# Main.net
KiCad netlist of a schematic drawn in Altium Designer
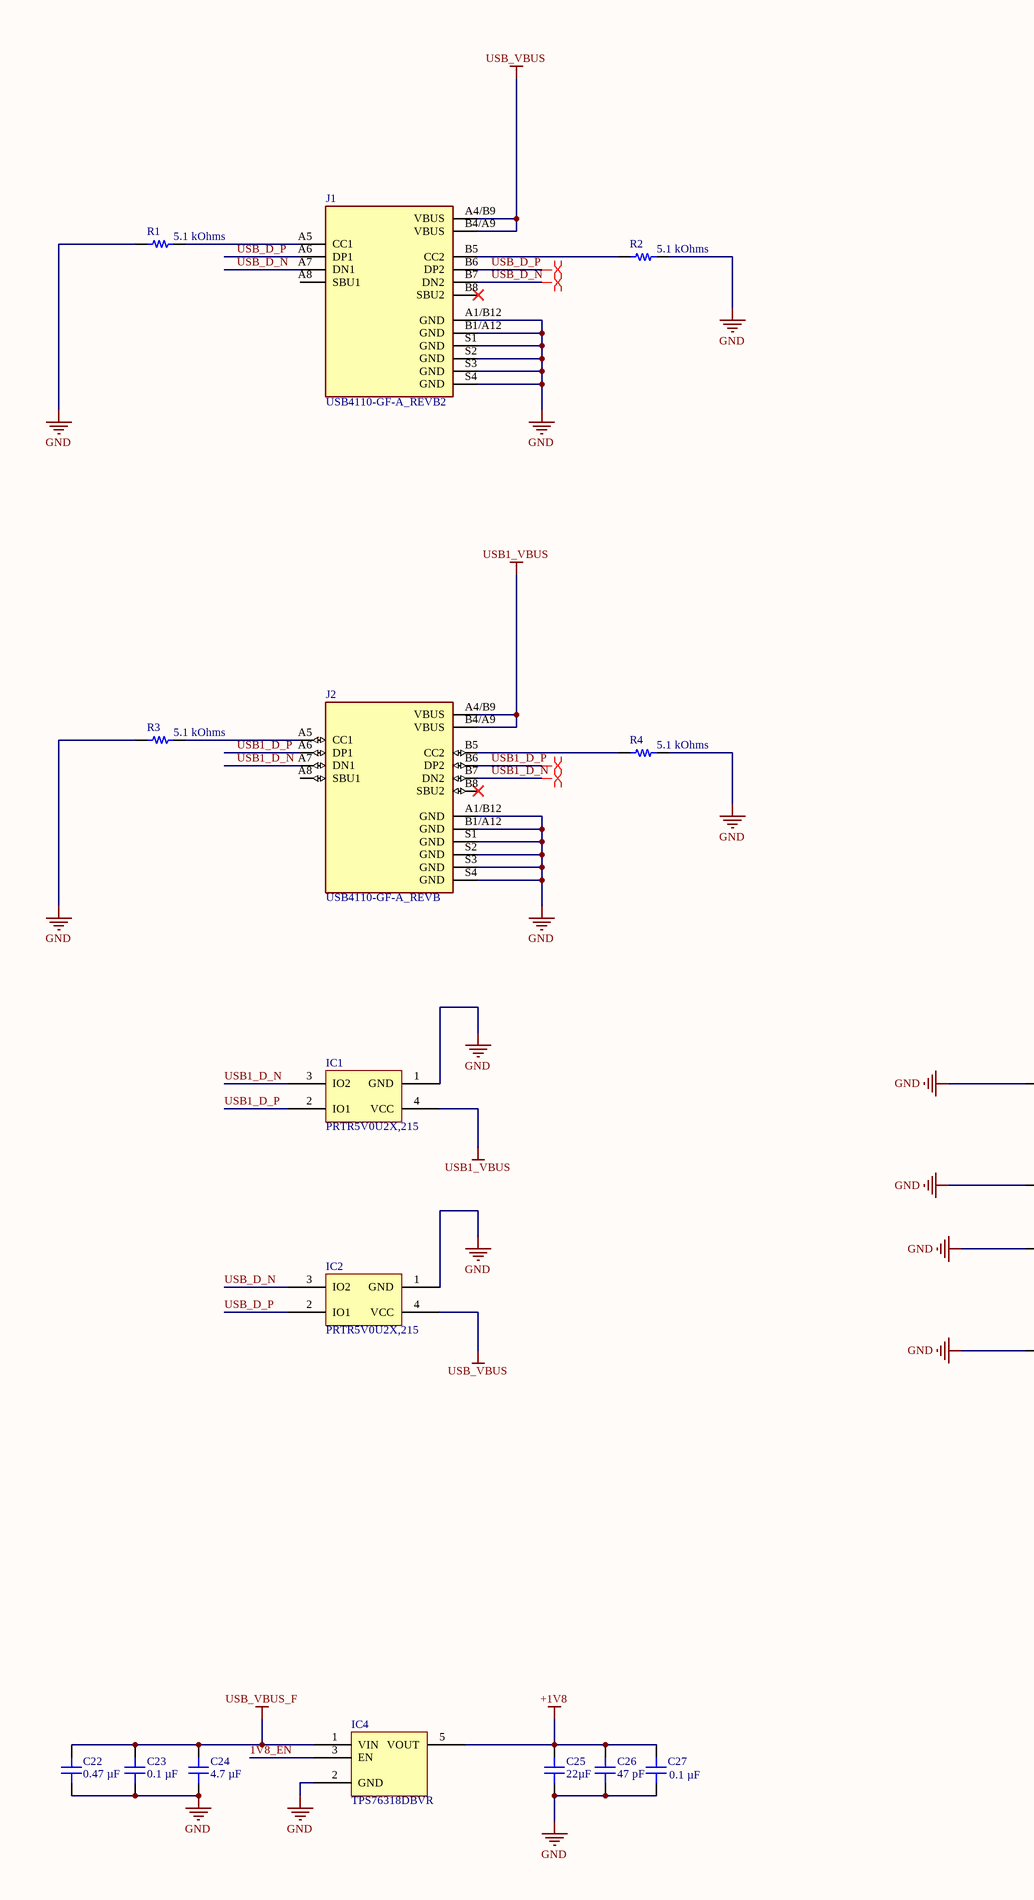
[diagram p0: Main.SchDoc, left]
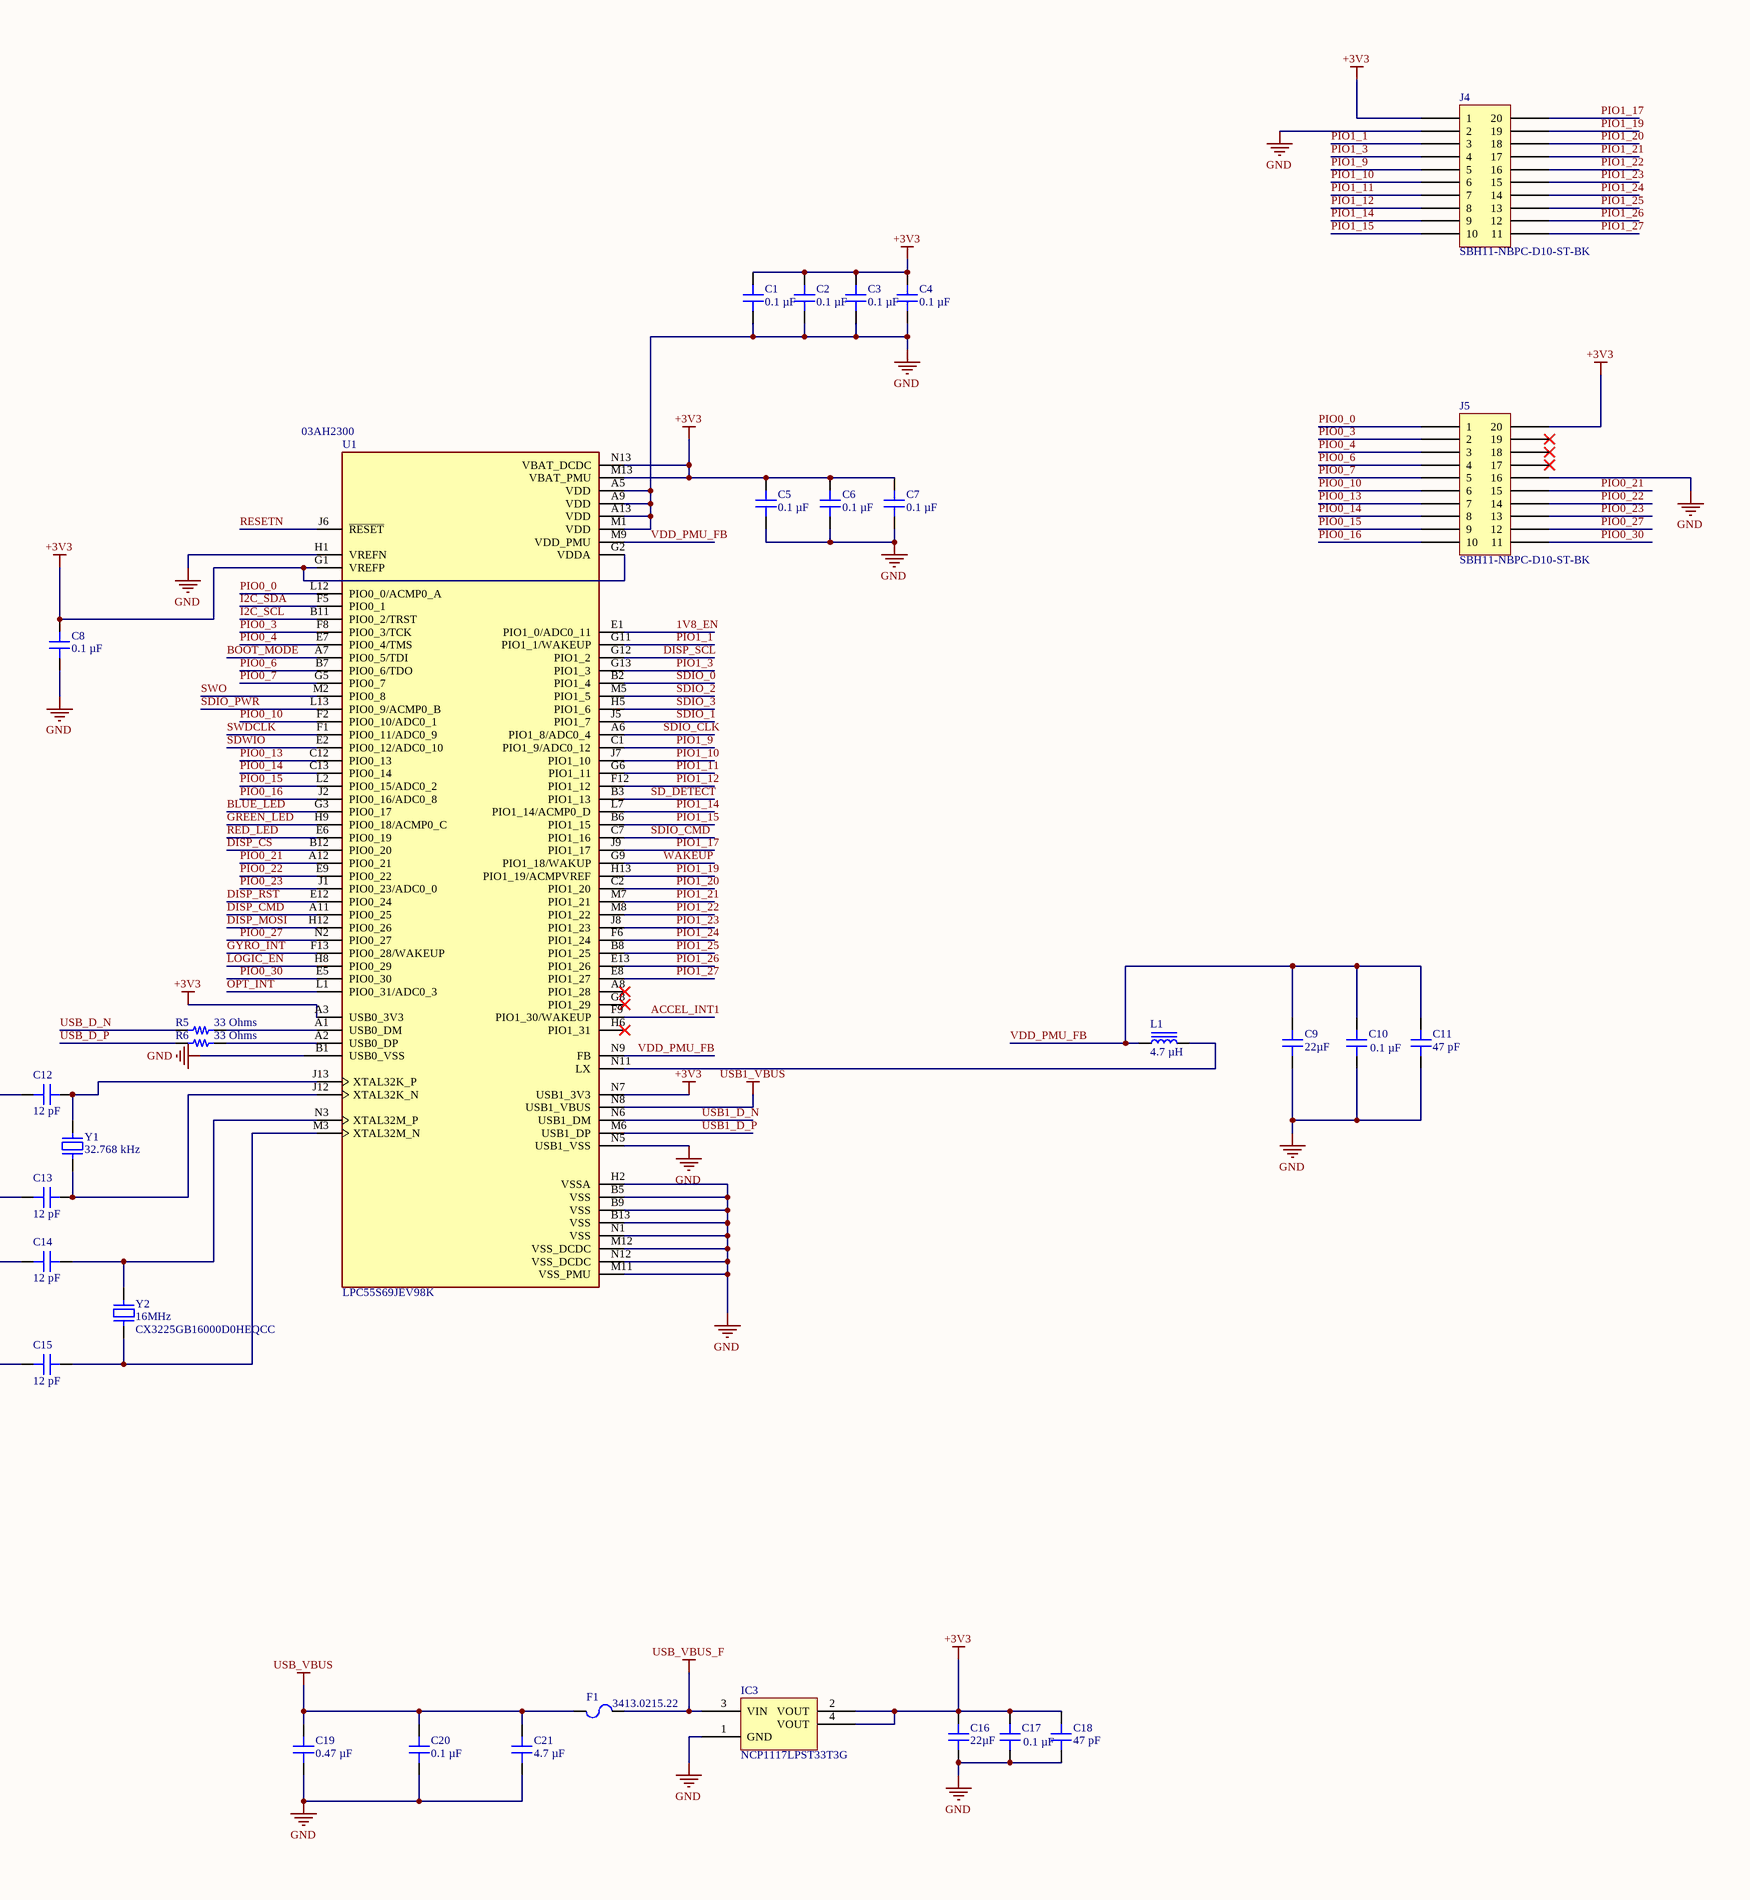
[diagram p1: Main.SchDoc, right]

(export (version "E")
  (design (tool "Eeschema 10.0.6"))
  (components
    (comp (ref "C1")
      (value "0.1 µF")
      (footprint "CAP 0603_1608")
      (description "CAP CER 0.1UF 16V X7R 0603")
      (fields (field (name "PART NUMBER") "CS0603KRX7R7BB104") (field (name "MANUFACTURER") "Yageo"))
      (libsource (lib "Celestial Altium Library - altium_library") (part "Capacitor"))
    )
    (comp (ref "C2")
      (value "0.1 µF")
      (footprint "CAP 0603_1608")
      (description "CAP CER 0.1UF 16V X7R 0603")
      (fields (field (name "PART NUMBER") "CS0603KRX7R7BB104") (field (name "MANUFACTURER") "Yageo"))
      (libsource (lib "Celestial Altium Library - altium_library") (part "Capacitor"))
    )
    (comp (ref "C3")
      (value "0.1 µF")
      (footprint "CAP 0603_1608")
      (description "CAP CER 0.1UF 16V X7R 0603")
      (fields (field (name "PART NUMBER") "CS0603KRX7R7BB104") (field (name "MANUFACTURER") "Yageo"))
      (libsource (lib "Celestial Altium Library - altium_library") (part "Capacitor"))
    )
    (comp (ref "C4")
      (value "0.1 µF")
      (footprint "CAP 0603_1608")
      (description "CAP CER 0.1UF 16V X7R 0603")
      (fields (field (name "PART NUMBER") "CS0603KRX7R7BB104") (field (name "MANUFACTURER") "Yageo"))
      (libsource (lib "Celestial Altium Library - altium_library") (part "Capacitor"))
    )
    (comp (ref "C5")
      (value "0.1 µF")
      (footprint "CAP 0603_1608")
      (description "CAP CER 0.1UF 16V X7R 0603")
      (fields (field (name "PART NUMBER") "CS0603KRX7R7BB104") (field (name "MANUFACTURER") "Yageo"))
      (libsource (lib "Celestial Altium Library - altium_library") (part "Capacitor"))
    )
    (comp (ref "C6")
      (value "0.1 µF")
      (footprint "CAP 0603_1608")
      (description "CAP CER 0.1UF 16V X7R 0603")
      (fields (field (name "PART NUMBER") "CS0603KRX7R7BB104") (field (name "MANUFACTURER") "Yageo"))
      (libsource (lib "Celestial Altium Library - altium_library") (part "Capacitor"))
    )
    (comp (ref "C7")
      (value "0.1 µF")
      (footprint "CAP 0603_1608")
      (description "CAP CER 0.1UF 16V X7R 0603")
      (fields (field (name "PART NUMBER") "CS0603KRX7R7BB104") (field (name "MANUFACTURER") "Yageo"))
      (libsource (lib "Celestial Altium Library - altium_library") (part "Capacitor"))
    )
    (comp (ref "C8")
      (value "0.1 µF")
      (footprint "CAP 0603_1608")
      (description "CAP CER 0.1UF 16V X7R 0603")
      (fields (field (name "PART NUMBER") "CS0603KRX7R7BB104") (field (name "MANUFACTURER") "Yageo"))
      (libsource (lib "Celestial Altium Library - altium_library") (part "Capacitor"))
    )
    (comp (ref "C9")
      (value "22µF")
      (footprint "CAP 0603_1608")
      (description "CAP CER 22UF 6.3V X5R 0603")
      (fields (field (name "PART NUMBER") "06036D226MAT2A") (field (name "MANUFACTURER") "AVX Corporation"))
      (libsource (lib "Celestial Altium Library - altium_library") (part "Capacitor"))
    )
    (comp (ref "C10")
      (value "0.1 µF")
      (footprint "CAP 0603_1608")
      (description "CAP CER 0.1UF 16V X7R 0603")
      (fields (field (name "PART NUMBER") "CS0603KRX7R7BB104") (field (name "MANUFACTURER") "Yageo"))
      (libsource (lib "Celestial Altium Library - altium_library") (part "Capacitor"))
    )
    (comp (ref "C11")
      (value "47 pF")
      (footprint "CAP 0603_1608")
      (description "CAP CER 47PF 25V C0G/NP0 0603")
      (fields (field (name "PART NUMBER") "C0603C470J3GACAUTO") (field (name "MANUFACTURER") "KEMET"))
      (libsource (lib "Celestial Altium Library - altium_library") (part "Capacitor"))
    )
    (comp (ref "C12")
      (value "12 pF")
      (footprint "CAP 0603_1608")
      (description "CAP CER 12PF 50V C0G/NPO 0603")
      (fields (field (name "PART NUMBER") "CC0603GRNPO9BN120") (field (name "MANUFACTURER") "Yageo"))
      (libsource (lib "Celestial Altium Library - altium_library") (part "Capacitor"))
    )
    (comp (ref "C13")
      (value "12 pF")
      (footprint "CAP 0603_1608")
      (description "CAP CER 12PF 50V C0G/NPO 0603")
      (fields (field (name "PART NUMBER") "CC0603GRNPO9BN120") (field (name "MANUFACTURER") "Yageo"))
      (libsource (lib "Celestial Altium Library - altium_library") (part "Capacitor"))
    )
    (comp (ref "C14")
      (value "12 pF")
      (footprint "CAP 0603_1608")
      (description "CAP CER 12PF 50V C0G/NPO 0603")
      (fields (field (name "PART NUMBER") "CC0603GRNPO9BN120") (field (name "MANUFACTURER") "Yageo"))
      (libsource (lib "Celestial Altium Library - altium_library") (part "Capacitor"))
    )
    (comp (ref "C15")
      (value "12 pF")
      (footprint "CAP 0603_1608")
      (description "CAP CER 12PF 50V C0G/NPO 0603")
      (fields (field (name "PART NUMBER") "CC0603GRNPO9BN120") (field (name "MANUFACTURER") "Yageo"))
      (libsource (lib "Celestial Altium Library - altium_library") (part "Capacitor"))
    )
    (comp (ref "C16")
      (value "22µF")
      (footprint "CAP 0603_1608")
      (description "CAP CER 22UF 6.3V X5R 0603")
      (fields (field (name "PART NUMBER") "06036D226MAT2A") (field (name "MANUFACTURER") "AVX Corporation"))
      (libsource (lib "Celestial Altium Library - altium_library") (part "Capacitor"))
    )
    (comp (ref "C17")
      (value "0.1 µF")
      (footprint "CAP 0603_1608")
      (description "CAP CER 0.1UF 16V X7R 0603")
      (fields (field (name "PART NUMBER") "CS0603KRX7R7BB104") (field (name "MANUFACTURER") "Yageo"))
      (libsource (lib "Celestial Altium Library - altium_library") (part "Capacitor"))
    )
    (comp (ref "C18")
      (value "47 pF")
      (footprint "CAP 0603_1608")
      (description "CAP CER 47PF 25V C0G/NP0 0603")
      (fields (field (name "PART NUMBER") "C0603C470J3GACAUTO") (field (name "MANUFACTURER") "KEMET"))
      (libsource (lib "Celestial Altium Library - altium_library") (part "Capacitor"))
    )
    (comp (ref "C19")
      (value "0.47 µF")
      (footprint "CAP 0603_1608")
      (description "CAP CER 0.47UF 10V X5R 0603")
      (fields (field (name "PART NUMBER") "CC0603KRX5R6BB474") (field (name "MANUFACTURER") "Yageo"))
      (libsource (lib "Celestial Altium Library - altium_library") (part "Capacitor"))
    )
    (comp (ref "C20")
      (value "0.1 µF")
      (footprint "CAP 0603_1608")
      (description "CAP CER 0.1UF 16V X7R 0603")
      (fields (field (name "PART NUMBER") "CS0603KRX7R7BB104") (field (name "MANUFACTURER") "Yageo"))
      (libsource (lib "Celestial Altium Library - altium_library") (part "Capacitor"))
    )
    (comp (ref "C21")
      (value "4.7 µF")
      (footprint "CAP 0603_1608")
      (description "CAP CER 4.7UF 10V X7S 0603")
      (fields
        (field (name "PART NUMBER") "GRM188C71A475KE11D")
        (field (name "MANUFACTURER") "Murata Electronics")
      )
      (libsource (lib "Celestial Altium Library - altium_library") (part "Capacitor"))
    )
    (comp (ref "C22")
      (value "0.47 µF")
      (footprint "CAP 0603_1608")
      (description "CAP CER 0.47UF 10V X5R 0603")
      (fields (field (name "PART NUMBER") "CC0603KRX5R6BB474") (field (name "MANUFACTURER") "Yageo"))
      (libsource (lib "Celestial Altium Library - altium_library") (part "Capacitor"))
    )
    (comp (ref "C23")
      (value "0.1 µF")
      (footprint "CAP 0603_1608")
      (description "CAP CER 0.1UF 16V X7R 0603")
      (fields (field (name "PART NUMBER") "CS0603KRX7R7BB104") (field (name "MANUFACTURER") "Yageo"))
      (libsource (lib "Celestial Altium Library - altium_library") (part "Capacitor"))
    )
    (comp (ref "C24")
      (value "4.7 µF")
      (footprint "CAP 0603_1608")
      (description "CAP CER 4.7UF 10V X7S 0603")
      (fields
        (field (name "PART NUMBER") "GRM188C71A475KE11D")
        (field (name "MANUFACTURER") "Murata Electronics")
      )
      (libsource (lib "Celestial Altium Library - altium_library") (part "Capacitor"))
    )
    (comp (ref "C25")
      (value "22µF")
      (footprint "CAP 0603_1608")
      (description "CAP CER 22UF 6.3V X5R 0603")
      (fields (field (name "PART NUMBER") "06036D226MAT2A") (field (name "MANUFACTURER") "AVX Corporation"))
      (libsource (lib "Celestial Altium Library - altium_library") (part "Capacitor"))
    )
    (comp (ref "C26")
      (value "47 pF")
      (footprint "CAP 0603_1608")
      (description "CAP CER 47PF 25V C0G/NP0 0603")
      (fields (field (name "PART NUMBER") "C0603C470J3GACAUTO") (field (name "MANUFACTURER") "KEMET"))
      (libsource (lib "Celestial Altium Library - altium_library") (part "Capacitor"))
    )
    (comp (ref "C27")
      (value "0.1 µF")
      (footprint "CAP 0603_1608")
      (description "CAP CER 0.1UF 16V X7R 0603")
      (fields (field (name "PART NUMBER") "CS0603KRX7R7BB104") (field (name "MANUFACTURER") "Yageo"))
      (libsource (lib "Celestial Altium Library - altium_library") (part "Capacitor"))
    )
    (comp (ref "F1")
      (value "3413.0215.22")
      (footprint "FUSE 1206_3216 0.6MM")
      (description "FUSE BOARD MNT 800MA 32VAC 63VDC")
      (fields (field (name "MANUFACTURER") "Schurter Inc."))
      (libsource (lib "Celestial Altium Library - altium_library") (part "MOUNTED FUSE"))
    )
    (comp (ref "IC1")
      (value "PRTR5V0U2X,215")
      (footprint "SOT143B")
      (description "TVS DIODE 5.5V SOT143B")
      (fields (field (name "MANUFACTURER") "Nexperia USA Inc."))
      (libsource (lib "Celestial Altium Library - altium_library") (part "NXP PRTR5V0U2X"))
    )
    (comp (ref "IC2")
      (value "PRTR5V0U2X,215")
      (footprint "SOT143B")
      (description "TVS DIODE 5.5V SOT143B")
      (fields (field (name "MANUFACTURER") "Nexperia USA Inc."))
      (libsource (lib "Celestial Altium Library - altium_library") (part "NXP PRTR5V0U2X"))
    )
    (comp (ref "IC3")
      (value "NCP1117LPST33T3G")
      (footprint "ON SEMI SOT-223 ST(318H)")
      (description "IC REG LINEAR 3.3V 1A SOT223")
      (fields (field (name "MANUFACTURER") "ON Semiconductor"))
      (libsource (lib "Celestial Altium Library - altium_library") (part "ON Semi NCP1117"))
    )
    (comp (ref "IC4")
      (value "TPS76318DBVR")
      (footprint "TI SOT-23-5 DBV")
      (description "IC REG LINEAR 1.8V 150MA SOT23-5")
      (fields (field (name "MANUFACTURER") "Texas Instruments"))
      (libsource (lib "Celestial Altium Library - altium_library") (part "TI TPS763xx"))
    )
    (comp (ref "J1")
      (value "USB4110-GF-A_REVB2")
      (footprint "USBNew:USBNew")
      (description "USB")
      (fields (field (name "MP") "USB4110-GF-A_REVB"))
      (libsource (lib "USB4110-GF-A_REVB") (part "USB4110-GF-A_REVB"))
    )
    (comp (ref "J2")
      (value "USB4110-GF-A_REVB")
      (footprint "GCT_USB4110-GF-A_REVB")
      (description "USB")
      (libsource (lib "") (part "USB4110-GF-A_REVB_1"))
    )
    (comp (ref "J4")
      (value "SBH11-NBPC-D10-ST-BK")
      (footprint "SULLINS SBH11-NBPC-D10-ST-BK")
      (description "CONN HEADER VERT 20POS 2.54MM")
      (fields (field (name "MANUFACTURER") "Sullins Connector Solutions"))
      (libsource (lib "Celestial Altium Library - altium_library") (part "20 Pin Dual Row"))
    )
    (comp (ref "J5")
      (value "SBH11-NBPC-D10-ST-BK")
      (footprint "SULLINS SBH11-NBPC-D10-ST-BK")
      (description "CONN HEADER VERT 20POS 2.54MM")
      (fields (field (name "MANUFACTURER") "Sullins Connector Solutions"))
      (libsource (lib "Celestial Altium Library - altium_library") (part "20 Pin Dual Row"))
    )
    (comp (ref "L1")
      (value "4.7 µH")
      (footprint "TDK VLS252012CX")
      (description "FIXED IND 4.7UH 1.24A 210MOHM SM")
      (fields
        (field (name "PART NUMBER") "VLS252012CX-4R7M-1")
        (field (name "MANUFACTURER") "TDK Corporation")
      )
      (libsource (lib "Celestial Altium Library - altium_library") (part "Inductor"))
    )
    (comp (ref "R1")
      (value "5.1 kOhms")
      (footprint "RES 0603_1608")
      (description "RES SMD 5.1K OHM 5% 1/10W 0603")
      (fields (field (name "PART NUMBER") "AC0603JR-075K1L") (field (name "MANUFACTURER") "Yageo"))
      (libsource (lib "Celestial Altium Library - altium_library") (part "Resistor"))
    )
    (comp (ref "R2")
      (value "5.1 kOhms")
      (footprint "RES 0603_1608")
      (description "RES SMD 5.1K OHM 5% 1/10W 0603")
      (fields (field (name "PART NUMBER") "AC0603JR-075K1L") (field (name "MANUFACTURER") "Yageo"))
      (libsource (lib "Celestial Altium Library - altium_library") (part "Resistor"))
    )
    (comp (ref "R3")
      (value "5.1 kOhms")
      (footprint "RES 0603_1608")
      (description "RES SMD 5.1K OHM 5% 1/10W 0603")
      (fields (field (name "PART NUMBER") "AC0603JR-075K1L") (field (name "MANUFACTURER") "Yageo"))
      (libsource (lib "Celestial Altium Library - altium_library") (part "Resistor"))
    )
    (comp (ref "R4")
      (value "5.1 kOhms")
      (footprint "RES 0603_1608")
      (description "RES SMD 5.1K OHM 5% 1/10W 0603")
      (fields (field (name "PART NUMBER") "AC0603JR-075K1L") (field (name "MANUFACTURER") "Yageo"))
      (libsource (lib "Celestial Altium Library - altium_library") (part "Resistor"))
    )
    (comp (ref "R5")
      (value "33 Ohms")
      (footprint "RES 0603_1608")
      (description "RES SMD 33 OHM 1% 1/10W 0603")
      (fields (field (name "PART NUMBER") "AC0603FR-0733RL") (field (name "MANUFACTURER") "Yageo"))
      (libsource (lib "Celestial Altium Library - altium_library") (part "Resistor"))
    )
    (comp (ref "R6")
      (value "33 Ohms")
      (footprint "RES 0603_1608")
      (description "RES SMD 33 OHM 1% 1/10W 0603")
      (fields (field (name "PART NUMBER") "AC0603FR-0733RL") (field (name "MANUFACTURER") "Yageo"))
      (libsource (lib "Celestial Altium Library - altium_library") (part "Resistor"))
    )
    (comp (ref "U1")
      (value "LPC55S69JEV98K")
      (footprint "IC_LPC55S69JEV98K")
      (description "MCU 32-bit ARM Cortex M33 RISC 640KB Flash 3.3V 98-Pin VFBGA Tray")
      (fields (field (name "MF") "NXP Semiconductors") (field (name "SUPPLIER PART NUMBER 1") "03AH2300"))
      (libsource (lib "LPC55S69JEV98K") (part "LPC55S69JEV98K"))
    )
    (comp (ref "Y1")
      (value "32.768 kHz")
      (footprint "ABRACON ABS06")
      (description "CRYSTAL 32.7680KHZ 12.5PF SMD")
      (fields (field (name "PART NUMBER") "ABS06-32.768KHZ-1-T") (field (name "MANUFACTURER") "Abracon LLC"))
      (libsource (lib "Celestial Altium Library - altium_library") (part "Abracon Crystal ABS06"))
    )
    (comp (ref "Y2")
      (value "16MHz")
      (footprint "KYOCERA CX3225GB")
      (description "CRYSTAL 16.0000MHZ 8PF SMD")
      (fields
        (field (name "PART NUMBER") "CX3225GB16000D0HEQCC")
        (field (name "MANUFACTURER") "Kyocera International Inc. Electronic Components")
      )
      (libsource (lib "Celestial Altium Library - altium_library") (part "Kyocera Crystal CX3225GB"))
    )
  )
  (nets
    (net (code "1") (name "+1V8") (class "Default")
      (node (ref "C25") (pin "1") (pinfunction "1_1") (pintype "passive"))
      (node (ref "C26") (pin "2") (pinfunction "2_2") (pintype "passive"))
      (node (ref "C27") (pin "2") (pinfunction "2_2") (pintype "passive"))
      (node (ref "IC4") (pin "5") (pinfunction "VOUT_5") (pintype "passive"))
    )
    (net (code "2") (name "+3V3") (class "Default")
      (node (ref "C1") (pin "2") (pinfunction "2_2") (pintype "passive"))
      (node (ref "C16") (pin "1") (pinfunction "1_1") (pintype "passive"))
      (node (ref "C17") (pin "2") (pinfunction "2_2") (pintype "passive"))
      (node (ref "C18") (pin "2") (pinfunction "2_2") (pintype "passive"))
      (node (ref "C2") (pin "2") (pinfunction "2_2") (pintype "passive"))
      (node (ref "C3") (pin "2") (pinfunction "2_2") (pintype "passive"))
      (node (ref "C4") (pin "2") (pinfunction "2_2") (pintype "passive"))
      (node (ref "C5") (pin "2") (pinfunction "2_2") (pintype "passive"))
      (node (ref "C6") (pin "2") (pinfunction "2_2") (pintype "passive"))
      (node (ref "C7") (pin "2") (pinfunction "2_2") (pintype "passive"))
      (node (ref "C8") (pin "2") (pinfunction "2_2") (pintype "passive"))
      (node (ref "IC3") (pin "2") (pinfunction "VOUT_2") (pintype "passive"))
      (node (ref "IC3") (pin "4") (pinfunction "VOUT_4") (pintype "passive"))
      (node (ref "J4") (pin "1") (pinfunction "1_1") (pintype "passive"))
      (node (ref "J5") (pin "20") (pinfunction "20_20") (pintype "passive"))
      (node (ref "U1") (pin "A3") (pinfunction "USB0_3V3_A3") (pintype "passive"))
      (node (ref "U1") (pin "G1") (pinfunction "VREFP_G1") (pintype "passive"))
      (node (ref "U1") (pin "G2") (pinfunction "VDDA_G2") (pintype "passive"))
      (node (ref "U1") (pin "M13") (pinfunction "VBAT_PMU_M13") (pintype "passive"))
      (node (ref "U1") (pin "N13") (pinfunction "VBAT_DCDC_N13") (pintype "passive"))
      (node (ref "U1") (pin "N7") (pinfunction "USB1_3V3_N7") (pintype "passive"))
    )
    (net (code "3") (name "/1V8_EN") (class "Default")
      (node (ref "IC4") (pin "3") (pinfunction "EN_3") (pintype "passive"))
      (node (ref "U1") (pin "E1") (pinfunction "PIO1_0/ADC0_11_E1") (pintype "passive"))
    )
    (net (code "4") (name "/ACCEL_INT1") (class "Default")
      (node (ref "U1") (pin "F9") (pinfunction "PIO1_30/WAKEUP_F9") (pintype "passive"))
    )
    (net (code "5") (name "/BLUE_LED") (class "Default")
      (node (ref "U1") (pin "G3") (pinfunction "PIO0_17_G3") (pintype "passive"))
    )
    (net (code "6") (name "/BOOT_MODE") (class "Default")
      (node (ref "U1") (pin "A7") (pinfunction "PIO0_5/TDI_A7") (pintype "passive"))
    )
    (net (code "7") (name "/DISP_CMD") (class "Default")
      (node (ref "U1") (pin "A11") (pinfunction "PIO0_25_A11") (pintype "passive"))
    )
    (net (code "8") (name "/DISP_CS") (class "Default")
      (node (ref "U1") (pin "B12") (pinfunction "PIO0_20_B12") (pintype "passive"))
    )
    (net (code "9") (name "/DISP_MOSI") (class "Default")
      (node (ref "U1") (pin "H12") (pinfunction "PIO0_26_H12") (pintype "passive"))
    )
    (net (code "10") (name "/DISP_RST") (class "Default")
      (node (ref "U1") (pin "E12") (pinfunction "PIO0_24_E12") (pintype "passive"))
    )
    (net (code "11") (name "/DISP_SCL") (class "Default")
      (node (ref "U1") (pin "G12") (pinfunction "PIO1_2_G12") (pintype "passive"))
    )
    (net (code "12") (name "/GREEN_LED") (class "Default")
      (node (ref "U1") (pin "H9") (pinfunction "PIO0_18/ACMP0_C_H9") (pintype "passive"))
    )
    (net (code "13") (name "/GYRO_INT") (class "Default")
      (node (ref "U1") (pin "F13") (pinfunction "PIO0_28/WAKEUP_F13") (pintype "passive"))
    )
    (net (code "14") (name "/I2C_SCL") (class "Default")
      (node (ref "U1") (pin "B11") (pinfunction "PIO0_2/TRST_B11") (pintype "passive"))
    )
    (net (code "15") (name "/I2C_SDA") (class "Default")
      (node (ref "U1") (pin "F5") (pinfunction "PIO0_1_F5") (pintype "passive"))
    )
    (net (code "16") (name "/LOGIC_EN") (class "Default")
      (node (ref "U1") (pin "H8") (pinfunction "PIO0_29_H8") (pintype "passive"))
    )
    (net (code "17") (name "/OPT_INT") (class "Default")
      (node (ref "U1") (pin "L1") (pinfunction "PIO0_31/ADC0_3_L1") (pintype "passive"))
    )
    (net (code "18") (name "/PIO0_0") (class "Default")
      (node (ref "J5") (pin "1") (pinfunction "1_1") (pintype "passive"))
      (node (ref "U1") (pin "L12") (pinfunction "PIO0_0/ACMP0_A_L12") (pintype "passive"))
    )
    (net (code "19") (name "/PIO0_3") (class "Default")
      (node (ref "J5") (pin "2") (pinfunction "2_2") (pintype "passive"))
      (node (ref "U1") (pin "F8") (pinfunction "PIO0_3/TCK_F8") (pintype "passive"))
    )
    (net (code "20") (name "/PIO0_4") (class "Default")
      (node (ref "J5") (pin "3") (pinfunction "3_3") (pintype "passive"))
      (node (ref "U1") (pin "E7") (pinfunction "PIO0_4/TMS_E7") (pintype "passive"))
    )
    (net (code "21") (name "/PIO0_6") (class "Default")
      (node (ref "J5") (pin "4") (pinfunction "4_4") (pintype "passive"))
      (node (ref "U1") (pin "B7") (pinfunction "PIO0_6/TDO_B7") (pintype "passive"))
    )
    (net (code "22") (name "/PIO0_7") (class "Default")
      (node (ref "J5") (pin "5") (pinfunction "5_5") (pintype "passive"))
      (node (ref "U1") (pin "G5") (pinfunction "PIO0_7_G5") (pintype "passive"))
    )
    (net (code "23") (name "/PIO0_10") (class "Default")
      (node (ref "J5") (pin "6") (pinfunction "6_6") (pintype "passive"))
      (node (ref "U1") (pin "F2") (pinfunction "PIO0_10/ADC0_1_F2") (pintype "passive"))
    )
    (net (code "24") (name "/PIO0_13") (class "Default")
      (node (ref "J5") (pin "7") (pinfunction "7_7") (pintype "passive"))
      (node (ref "U1") (pin "C12") (pinfunction "PIO0_13_C12") (pintype "passive"))
    )
    (net (code "25") (name "/PIO0_14") (class "Default")
      (node (ref "J5") (pin "8") (pinfunction "8_8") (pintype "passive"))
      (node (ref "U1") (pin "C13") (pinfunction "PIO0_14_C13") (pintype "passive"))
    )
    (net (code "26") (name "/PIO0_15") (class "Default")
      (node (ref "J5") (pin "9") (pinfunction "9_9") (pintype "passive"))
      (node (ref "U1") (pin "L2") (pinfunction "PIO0_15/ADC0_2_L2") (pintype "passive"))
    )
    (net (code "27") (name "/PIO0_16") (class "Default")
      (node (ref "J5") (pin "10") (pinfunction "10_10") (pintype "passive"))
      (node (ref "U1") (pin "J2") (pinfunction "PIO0_16/ADC0_8_J2") (pintype "passive"))
    )
    (net (code "28") (name "/PIO0_21") (class "Default")
      (node (ref "J5") (pin "15") (pinfunction "15_15") (pintype "passive"))
      (node (ref "U1") (pin "A12") (pinfunction "PIO0_21_A12") (pintype "passive"))
    )
    (net (code "29") (name "/PIO0_22") (class "Default")
      (node (ref "J5") (pin "14") (pinfunction "14_14") (pintype "passive"))
      (node (ref "U1") (pin "E9") (pinfunction "PIO0_22_E9") (pintype "passive"))
    )
    (net (code "30") (name "/PIO0_23") (class "Default")
      (node (ref "J5") (pin "13") (pinfunction "13_13") (pintype "passive"))
      (node (ref "U1") (pin "J1") (pinfunction "PIO0_23/ADC0_0_J1") (pintype "passive"))
    )
    (net (code "31") (name "/PIO0_27") (class "Default")
      (node (ref "J5") (pin "12") (pinfunction "12_12") (pintype "passive"))
      (node (ref "U1") (pin "N2") (pinfunction "PIO0_27_N2") (pintype "passive"))
    )
    (net (code "32") (name "/PIO0_30") (class "Default")
      (node (ref "J5") (pin "11") (pinfunction "11_11") (pintype "passive"))
      (node (ref "U1") (pin "E5") (pinfunction "PIO0_30_E5") (pintype "passive"))
    )
    (net (code "33") (name "/PIO1_1") (class "Default")
      (node (ref "J4") (pin "3") (pinfunction "3_3") (pintype "passive"))
      (node (ref "U1") (pin "G11") (pinfunction "PIO1_1/WAKEUP_G11") (pintype "passive"))
    )
    (net (code "34") (name "/PIO1_3") (class "Default")
      (node (ref "J4") (pin "4") (pinfunction "4_4") (pintype "passive"))
      (node (ref "U1") (pin "G13") (pinfunction "PIO1_3_G13") (pintype "passive"))
    )
    (net (code "35") (name "/PIO1_9") (class "Default")
      (node (ref "J4") (pin "5") (pinfunction "5_5") (pintype "passive"))
      (node (ref "U1") (pin "C1") (pinfunction "PIO1_9/ADC0_12_C1") (pintype "passive"))
    )
    (net (code "36") (name "/PIO1_10") (class "Default")
      (node (ref "J4") (pin "6") (pinfunction "6_6") (pintype "passive"))
      (node (ref "U1") (pin "J7") (pinfunction "PIO1_10_J7") (pintype "passive"))
    )
    (net (code "37") (name "/PIO1_11") (class "Default")
      (node (ref "J4") (pin "7") (pinfunction "7_7") (pintype "passive"))
      (node (ref "U1") (pin "G6") (pinfunction "PIO1_11_G6") (pintype "passive"))
    )
    (net (code "38") (name "/PIO1_12") (class "Default")
      (node (ref "J4") (pin "8") (pinfunction "8_8") (pintype "passive"))
      (node (ref "U1") (pin "F12") (pinfunction "PIO1_12_F12") (pintype "passive"))
    )
    (net (code "39") (name "/PIO1_14") (class "Default")
      (node (ref "J4") (pin "9") (pinfunction "9_9") (pintype "passive"))
      (node (ref "U1") (pin "L7") (pinfunction "PIO1_14/ACMP0_D_L7") (pintype "passive"))
    )
    (net (code "40") (name "/PIO1_15") (class "Default")
      (node (ref "J4") (pin "10") (pinfunction "10_10") (pintype "passive"))
      (node (ref "U1") (pin "B6") (pinfunction "PIO1_15_B6") (pintype "passive"))
    )
    (net (code "41") (name "/PIO1_17") (class "Default")
      (node (ref "J4") (pin "20") (pinfunction "20_20") (pintype "passive"))
      (node (ref "U1") (pin "J9") (pinfunction "PIO1_17_J9") (pintype "passive"))
    )
    (net (code "42") (name "/PIO1_19") (class "Default")
      (node (ref "J4") (pin "19") (pinfunction "19_19") (pintype "passive"))
      (node (ref "U1") (pin "H13") (pinfunction "PIO1_19/ACMPVREF_H13") (pintype "passive"))
    )
    (net (code "43") (name "/PIO1_20") (class "Default")
      (node (ref "J4") (pin "18") (pinfunction "18_18") (pintype "passive"))
      (node (ref "U1") (pin "C2") (pinfunction "PIO1_20_C2") (pintype "passive"))
    )
    (net (code "44") (name "/PIO1_21") (class "Default")
      (node (ref "J4") (pin "17") (pinfunction "17_17") (pintype "passive"))
      (node (ref "U1") (pin "M7") (pinfunction "PIO1_21_M7") (pintype "passive"))
    )
    (net (code "45") (name "/PIO1_22") (class "Default")
      (node (ref "J4") (pin "16") (pinfunction "16_16") (pintype "passive"))
      (node (ref "U1") (pin "M8") (pinfunction "PIO1_22_M8") (pintype "passive"))
    )
    (net (code "46") (name "/PIO1_23") (class "Default")
      (node (ref "J4") (pin "15") (pinfunction "15_15") (pintype "passive"))
      (node (ref "U1") (pin "J8") (pinfunction "PIO1_23_J8") (pintype "passive"))
    )
    (net (code "47") (name "/PIO1_24") (class "Default")
      (node (ref "J4") (pin "14") (pinfunction "14_14") (pintype "passive"))
      (node (ref "U1") (pin "F6") (pinfunction "PIO1_24_F6") (pintype "passive"))
    )
    (net (code "48") (name "/PIO1_25") (class "Default")
      (node (ref "J4") (pin "13") (pinfunction "13_13") (pintype "passive"))
      (node (ref "U1") (pin "B8") (pinfunction "PIO1_25_B8") (pintype "passive"))
    )
    (net (code "49") (name "/PIO1_26") (class "Default")
      (node (ref "J4") (pin "12") (pinfunction "12_12") (pintype "passive"))
      (node (ref "U1") (pin "E13") (pinfunction "PIO1_26_E13") (pintype "passive"))
    )
    (net (code "50") (name "/PIO1_27") (class "Default")
      (node (ref "J4") (pin "11") (pinfunction "11_11") (pintype "passive"))
      (node (ref "U1") (pin "E8") (pinfunction "PIO1_27_E8") (pintype "passive"))
    )
    (net (code "51") (name "/RED_LED") (class "Default")
      (node (ref "U1") (pin "E6") (pinfunction "PIO0_19_E6") (pintype "passive"))
    )
    (net (code "52") (name "/RESETN") (class "Default")
      (node (ref "U1") (pin "J6") (pinfunction "~{RESET}_J6") (pintype "passive"))
    )
    (net (code "53") (name "/SDIO_0") (class "Default")
      (node (ref "U1") (pin "B2") (pinfunction "PIO1_4_B2") (pintype "passive"))
    )
    (net (code "54") (name "/SDIO_1") (class "Default")
      (node (ref "U1") (pin "J5") (pinfunction "PIO1_7_J5") (pintype "passive"))
    )
    (net (code "55") (name "/SDIO_2") (class "Default")
      (node (ref "U1") (pin "M5") (pinfunction "PIO1_5_M5") (pintype "passive"))
    )
    (net (code "56") (name "/SDIO_3") (class "Default")
      (node (ref "U1") (pin "H5") (pinfunction "PIO1_6_H5") (pintype "passive"))
    )
    (net (code "57") (name "/SDIO_CLK") (class "Default")
      (node (ref "U1") (pin "A6") (pinfunction "PIO1_8/ADC0_4_A6") (pintype "passive"))
    )
    (net (code "58") (name "/SDIO_CMD") (class "Default")
      (node (ref "U1") (pin "C7") (pinfunction "PIO1_16_C7") (pintype "passive"))
    )
    (net (code "59") (name "/SDIO_PWR") (class "Default")
      (node (ref "U1") (pin "L13") (pinfunction "PIO0_9/ACMP0_B_L13") (pintype "passive"))
    )
    (net (code "60") (name "/SDWIO") (class "Default")
      (node (ref "U1") (pin "E2") (pinfunction "PIO0_12/ADC0_10_E2") (pintype "passive"))
    )
    (net (code "61") (name "/SD_DETECT") (class "Default")
      (node (ref "U1") (pin "B3") (pinfunction "PIO1_13_B3") (pintype "passive"))
    )
    (net (code "62") (name "/SWDCLK") (class "Default")
      (node (ref "U1") (pin "F1") (pinfunction "PIO0_11/ADC0_9_F1") (pintype "passive"))
    )
    (net (code "63") (name "/SWO") (class "Default")
      (node (ref "U1") (pin "M2") (pinfunction "PIO0_8_M2") (pintype "passive"))
    )
    (net (code "64") (name "/USB1_D_N") (class "Default")
      (node (ref "IC1") (pin "3") (pinfunction "IO2_3") (pintype "passive"))
      (node (ref "J2") (pin "A7") (pinfunction "DN1_A7") (pintype "bidirectional"))
      (node (ref "J2") (pin "B7") (pinfunction "DN2_B7") (pintype "bidirectional"))
      (node (ref "U1") (pin "N6") (pinfunction "USB1_DM_N6") (pintype "passive"))
    )
    (net (code "65") (name "/USB1_D_P") (class "Default")
      (node (ref "IC1") (pin "2") (pinfunction "IO1_2") (pintype "passive"))
      (node (ref "J2") (pin "A6") (pinfunction "DP1_A6") (pintype "bidirectional"))
      (node (ref "J2") (pin "B6") (pinfunction "DP2_B6") (pintype "bidirectional"))
      (node (ref "U1") (pin "M6") (pinfunction "USB1_DP_M6") (pintype "passive"))
    )
    (net (code "66") (name "/USB_D_N") (class "Default")
      (node (ref "IC2") (pin "3") (pinfunction "IO2_3") (pintype "passive"))
      (node (ref "J1") (pin "A7") (pinfunction "DN1_A7") (pintype "power_in"))
      (node (ref "J1") (pin "B7") (pinfunction "DN2_B7") (pintype "power_in"))
      (node (ref "R5") (pin "1") (pinfunction "1_1") (pintype "passive"))
    )
    (net (code "67") (name "/USB_D_P") (class "Default")
      (node (ref "IC2") (pin "2") (pinfunction "IO1_2") (pintype "passive"))
      (node (ref "J1") (pin "A6") (pinfunction "DP1_A6") (pintype "power_in"))
      (node (ref "J1") (pin "B6") (pinfunction "DP2_B6") (pintype "power_in"))
      (node (ref "R6") (pin "1") (pinfunction "1_1") (pintype "passive"))
    )
    (net (code "68") (name "/VDD_PMU_FB") (class "Default")
      (node (ref "C10") (pin "2") (pinfunction "2_2") (pintype "passive"))
      (node (ref "C11") (pin "2") (pinfunction "2_2") (pintype "passive"))
      (node (ref "C9") (pin "1") (pinfunction "1_1") (pintype "passive"))
      (node (ref "L1") (pin "1") (pinfunction "1_1") (pintype "passive"))
      (node (ref "U1") (pin "M9") (pinfunction "VDD_PMU_M9") (pintype "passive"))
      (node (ref "U1") (pin "N9") (pinfunction "FB_N9") (pintype "passive"))
    )
    (net (code "69") (name "/WAKEUP") (class "Default")
      (node (ref "U1") (pin "G9") (pinfunction "PIO1_18/WAKUP_G9") (pintype "passive"))
    )
    (net (code "70") (name "GND") (class "Default")
      (node (ref "C1") (pin "1") (pinfunction "1_1") (pintype "passive"))
      (node (ref "C10") (pin "1") (pinfunction "1_1") (pintype "passive"))
      (node (ref "C11") (pin "1") (pinfunction "1_1") (pintype "passive"))
      (node (ref "C12") (pin "2") (pinfunction "2_2") (pintype "passive"))
      (node (ref "C13") (pin "2") (pinfunction "2_2") (pintype "passive"))
      (node (ref "C14") (pin "2") (pinfunction "2_2") (pintype "passive"))
      (node (ref "C15") (pin "2") (pinfunction "2_2") (pintype "passive"))
      (node (ref "C16") (pin "2") (pinfunction "2_2") (pintype "passive"))
      (node (ref "C17") (pin "1") (pinfunction "1_1") (pintype "passive"))
      (node (ref "C18") (pin "1") (pinfunction "1_1") (pintype "passive"))
      (node (ref "C19") (pin "1") (pinfunction "1_1") (pintype "passive"))
      (node (ref "C2") (pin "1") (pinfunction "1_1") (pintype "passive"))
      (node (ref "C20") (pin "1") (pinfunction "1_1") (pintype "passive"))
      (node (ref "C21") (pin "1") (pinfunction "1_1") (pintype "passive"))
      (node (ref "C22") (pin "1") (pinfunction "1_1") (pintype "passive"))
      (node (ref "C23") (pin "1") (pinfunction "1_1") (pintype "passive"))
      (node (ref "C24") (pin "1") (pinfunction "1_1") (pintype "passive"))
      (node (ref "C25") (pin "2") (pinfunction "2_2") (pintype "passive"))
      (node (ref "C26") (pin "1") (pinfunction "1_1") (pintype "passive"))
      (node (ref "C27") (pin "1") (pinfunction "1_1") (pintype "passive"))
      (node (ref "C3") (pin "1") (pinfunction "1_1") (pintype "passive"))
      (node (ref "C4") (pin "1") (pinfunction "1_1") (pintype "passive"))
      (node (ref "C5") (pin "1") (pinfunction "1_1") (pintype "passive"))
      (node (ref "C6") (pin "1") (pinfunction "1_1") (pintype "passive"))
      (node (ref "C7") (pin "1") (pinfunction "1_1") (pintype "passive"))
      (node (ref "C8") (pin "1") (pinfunction "1_1") (pintype "passive"))
      (node (ref "C9") (pin "2") (pinfunction "2_2") (pintype "passive"))
      (node (ref "IC1") (pin "1") (pinfunction "GND_1") (pintype "passive"))
      (node (ref "IC2") (pin "1") (pinfunction "GND_1") (pintype "passive"))
      (node (ref "IC3") (pin "1") (pinfunction "GND_1") (pintype "passive"))
      (node (ref "IC4") (pin "2") (pinfunction "GND_2") (pintype "passive"))
      (node (ref "J1") (pin "A1/B12") (pinfunction "GND_A1/B12") (pintype "power_in"))
      (node (ref "J1") (pin "B1/A12") (pinfunction "GND_B1/A12") (pintype "power_in"))
      (node (ref "J1") (pin "S1") (pinfunction "GND_S1") (pintype "power_in"))
      (node (ref "J1") (pin "S2") (pinfunction "GND_S2") (pintype "power_in"))
      (node (ref "J1") (pin "S3") (pinfunction "GND_S3") (pintype "power_in"))
      (node (ref "J1") (pin "S4") (pinfunction "GND_S4") (pintype "power_in"))
      (node (ref "J2") (pin "A1/B12") (pinfunction "GND_A1/B12") (pintype "power_in"))
      (node (ref "J2") (pin "B1/A12") (pinfunction "GND_B1/A12") (pintype "power_in"))
      (node (ref "J2") (pin "S1") (pinfunction "GND_S1") (pintype "power_in"))
      (node (ref "J2") (pin "S2") (pinfunction "GND_S2") (pintype "power_in"))
      (node (ref "J2") (pin "S3") (pinfunction "GND_S3") (pintype "power_in"))
      (node (ref "J2") (pin "S4") (pinfunction "GND_S4") (pintype "power_in"))
      (node (ref "J4") (pin "2") (pinfunction "2_2") (pintype "passive"))
      (node (ref "J5") (pin "16") (pinfunction "16_16") (pintype "passive"))
      (node (ref "R1") (pin "1") (pinfunction "1_1") (pintype "passive"))
      (node (ref "R2") (pin "2") (pinfunction "2_2") (pintype "passive"))
      (node (ref "R3") (pin "1") (pinfunction "1_1") (pintype "passive"))
      (node (ref "R4") (pin "2") (pinfunction "2_2") (pintype "passive"))
      (node (ref "U1") (pin "A13") (pinfunction "VDD_A13") (pintype "passive"))
      (node (ref "U1") (pin "A5") (pinfunction "VDD_A5") (pintype "passive"))
      (node (ref "U1") (pin "A9") (pinfunction "VDD_A9") (pintype "passive"))
      (node (ref "U1") (pin "B1") (pinfunction "USB0_VSS_B1") (pintype "passive"))
      (node (ref "U1") (pin "B13") (pinfunction "VSS_B13") (pintype "passive"))
      (node (ref "U1") (pin "B5") (pinfunction "VSS_B5") (pintype "passive"))
      (node (ref "U1") (pin "B9") (pinfunction "VSS_B9") (pintype "passive"))
      (node (ref "U1") (pin "H1") (pinfunction "VREFN_H1") (pintype "passive"))
      (node (ref "U1") (pin "H2") (pinfunction "VSSA_H2") (pintype "passive"))
      (node (ref "U1") (pin "M1") (pinfunction "VDD_M1") (pintype "passive"))
      (node (ref "U1") (pin "M11") (pinfunction "VSS_PMU_M11") (pintype "passive"))
      (node (ref "U1") (pin "M12") (pinfunction "VSS_DCDC_M12") (pintype "passive"))
      (node (ref "U1") (pin "N1") (pinfunction "VSS_N1") (pintype "passive"))
      (node (ref "U1") (pin "N12") (pinfunction "VSS_DCDC_N12") (pintype "passive"))
      (node (ref "U1") (pin "N5") (pinfunction "USB1_VSS_N5") (pintype "passive"))
    )
    (net (code "71") (name "Net-(J1-CC1)") (class "Default")
      (node (ref "J1") (pin "A5") (pinfunction "CC1_A5") (pintype "power_in"))
      (node (ref "R1") (pin "2") (pinfunction "2_2") (pintype "passive"))
    )
    (net (code "72") (name "Net-(J1-CC2)") (class "Default")
      (node (ref "J1") (pin "B5") (pinfunction "CC2_B5") (pintype "power_in"))
      (node (ref "R2") (pin "1") (pinfunction "1_1") (pintype "passive"))
    )
    (net (code "73") (name "Net-(J2-CC1)") (class "Default")
      (node (ref "J2") (pin "A5") (pinfunction "CC1_A5") (pintype "bidirectional"))
      (node (ref "R3") (pin "2") (pinfunction "2_2") (pintype "passive"))
    )
    (net (code "74") (name "Net-(J2-CC2)") (class "Default")
      (node (ref "J2") (pin "B5") (pinfunction "CC2_B5") (pintype "bidirectional"))
      (node (ref "R4") (pin "1") (pinfunction "1_1") (pintype "passive"))
    )
    (net (code "75") (name "Net-(U1-LX)") (class "Default")
      (node (ref "L1") (pin "2") (pinfunction "2_2") (pintype "passive"))
      (node (ref "U1") (pin "N11") (pinfunction "LX_N11") (pintype "passive"))
    )
    (net (code "76") (name "Net-(U1-USB0_DM)") (class "Default")
      (node (ref "R5") (pin "2") (pinfunction "2_2") (pintype "passive"))
      (node (ref "U1") (pin "A1") (pinfunction "USB0_DM_A1") (pintype "passive"))
    )
    (net (code "77") (name "Net-(U1-USB0_DP)") (class "Default")
      (node (ref "R6") (pin "2") (pinfunction "2_2") (pintype "passive"))
      (node (ref "U1") (pin "A2") (pinfunction "USB0_DP_A2") (pintype "passive"))
    )
    (net (code "78") (name "Net-(U1-XTAL32K_N)") (class "Default")
      (node (ref "C13") (pin "1") (pinfunction "1_1") (pintype "passive"))
      (node (ref "U1") (pin "J12") (pinfunction "XTAL32K_N_J12") (pintype "passive"))
      (node (ref "Y1") (pin "1") (pinfunction "1_1") (pintype "passive"))
    )
    (net (code "79") (name "Net-(U1-XTAL32K_P)") (class "Default")
      (node (ref "C12") (pin "1") (pinfunction "1_1") (pintype "passive"))
      (node (ref "U1") (pin "J13") (pinfunction "XTAL32K_P_J13") (pintype "passive"))
      (node (ref "Y1") (pin "2") (pinfunction "2_2") (pintype "passive"))
    )
    (net (code "80") (name "Net-(U1-XTAL32M_N)") (class "Default")
      (node (ref "C15") (pin "1") (pinfunction "1_1") (pintype "passive"))
      (node (ref "U1") (pin "M3") (pinfunction "XTAL32M_N_M3") (pintype "passive"))
      (node (ref "Y2") (pin "3") (pinfunction "3_3") (pintype "passive"))
    )
    (net (code "81") (name "Net-(U1-XTAL32M_P)") (class "Default")
      (node (ref "C14") (pin "1") (pinfunction "1_1") (pintype "passive"))
      (node (ref "U1") (pin "N3") (pinfunction "XTAL32M_P_N3") (pintype "passive"))
      (node (ref "Y2") (pin "1") (pinfunction "1_1") (pintype "passive"))
    )
    (net (code "82") (name "USB1_VBUS") (class "Default")
      (node (ref "IC1") (pin "4") (pinfunction "VCC_4") (pintype "passive"))
      (node (ref "J2") (pin "A4/B9") (pinfunction "VBUS_A4/B9") (pintype "power_in"))
      (node (ref "J2") (pin "B4/A9") (pinfunction "VBUS_B4/A9") (pintype "power_in"))
      (node (ref "U1") (pin "N8") (pinfunction "USB1_VBUS_N8") (pintype "passive"))
    )
    (net (code "83") (name "USB_VBUS") (class "Default")
      (node (ref "C19") (pin "2") (pinfunction "2_2") (pintype "passive"))
      (node (ref "C20") (pin "2") (pinfunction "2_2") (pintype "passive"))
      (node (ref "C21") (pin "2") (pinfunction "2_2") (pintype "passive"))
      (node (ref "F1") (pin "1") (pintype "passive"))
      (node (ref "IC2") (pin "4") (pinfunction "VCC_4") (pintype "passive"))
      (node (ref "J1") (pin "A4/B9") (pinfunction "VBUS_A4/B9") (pintype "power_in"))
      (node (ref "J1") (pin "B4/A9") (pinfunction "VBUS_B4/A9") (pintype "power_in"))
    )
    (net (code "84") (name "USB_VBUS_F") (class "Default")
      (node (ref "C22") (pin "2") (pinfunction "2_2") (pintype "passive"))
      (node (ref "C23") (pin "2") (pinfunction "2_2") (pintype "passive"))
      (node (ref "C24") (pin "2") (pinfunction "2_2") (pintype "passive"))
      (node (ref "F1") (pin "2") (pintype "passive"))
      (node (ref "IC3") (pin "3") (pinfunction "VIN_3") (pintype "passive"))
      (node (ref "IC4") (pin "1") (pinfunction "VIN_1") (pintype "passive"))
    )
    (net (code "85") (name "unconnected-(J1-SBU1-PadA8)") (class "Default")
      (node (ref "J1") (pin "A8") (pinfunction "SBU1_A8") (pintype "power_in"))
    )
    (net (code "86") (name "unconnected-(J1-SBU2-PadB8)") (class "Default")
      (node (ref "J1") (pin "B8") (pinfunction "SBU2_B8") (pintype "power_in+no_connect"))
    )
    (net (code "87") (name "unconnected-(J2-SBU1-PadA8)") (class "Default")
      (node (ref "J2") (pin "A8") (pinfunction "SBU1_A8") (pintype "bidirectional"))
    )
    (net (code "88") (name "unconnected-(J2-SBU2-PadB8)") (class "Default")
      (node (ref "J2") (pin "B8") (pinfunction "SBU2_B8") (pintype "bidirectional+no_connect"))
    )
    (net (code "89") (name "unconnected-(J5-Pad17)") (class "Default")
      (node (ref "J5") (pin "17") (pinfunction "17_17") (pintype "passive+no_connect"))
    )
    (net (code "90") (name "unconnected-(J5-Pad18)") (class "Default")
      (node (ref "J5") (pin "18") (pinfunction "18_18") (pintype "passive+no_connect"))
    )
    (net (code "91") (name "unconnected-(J5-Pad19)") (class "Default")
      (node (ref "J5") (pin "19") (pinfunction "19_19") (pintype "passive+no_connect"))
    )
    (net (code "92") (name "unconnected-(U1-PIO1_28-PadA8)") (class "Default")
      (node (ref "U1") (pin "A8") (pinfunction "PIO1_28_A8") (pintype "passive+no_connect"))
    )
    (net (code "93") (name "unconnected-(U1-PIO1_29-PadG8)") (class "Default")
      (node (ref "U1") (pin "G8") (pinfunction "PIO1_29_G8") (pintype "passive+no_connect"))
    )
    (net (code "94") (name "unconnected-(U1-PIO1_31-PadH6)") (class "Default")
      (node (ref "U1") (pin "H6") (pinfunction "PIO1_31_H6") (pintype "passive+no_connect"))
    )
  )
)
